# OpenSesame.net
KiCad netlist of a schematic drawn in EAGLE
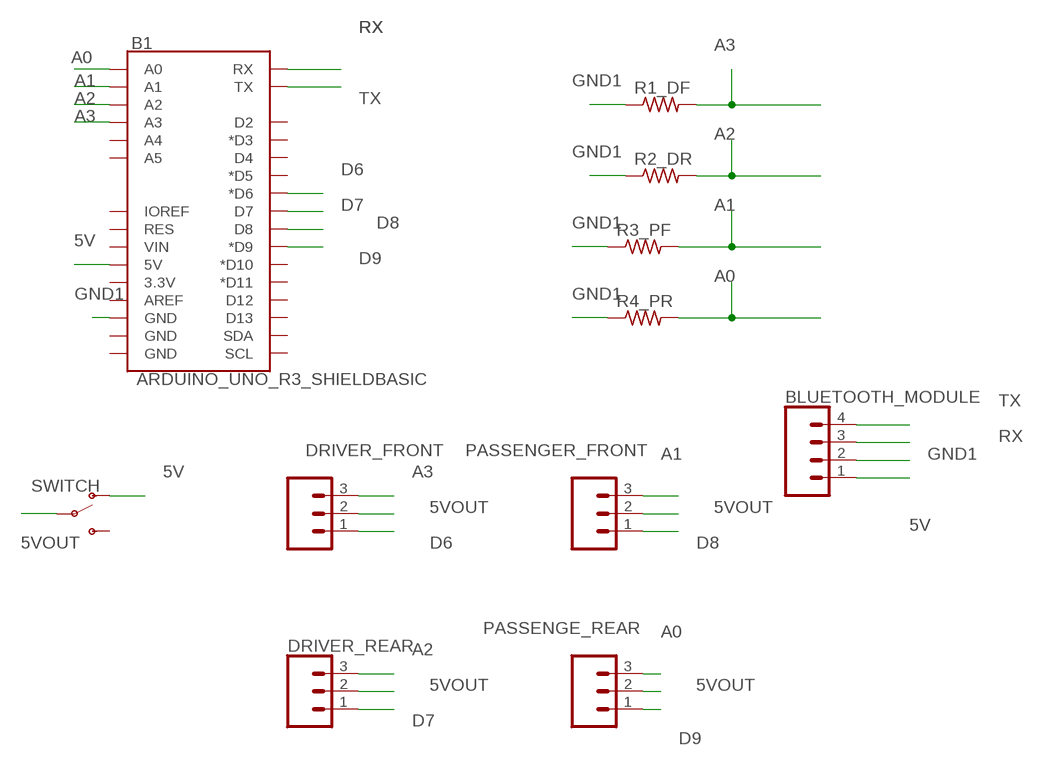
[diagram p0: schematic, sheet 1]

(export (version "E")
  (design (tool "Eeschema 10.0.6"))
  (components
    (comp (ref "B1")
      (value "ARDUINO_UNO_R3_SHIELDBASIC")
      (footprint "eagle-import:UNO_R3_SHIELD")
      (libsource (lib "eagle-import") (part "ARDUINO_UNO_R3_SHIELDBASIC"))
    )
    (comp (ref "BLUETOOTH_MODULE")
      (value "CONN_04")
      (footprint "eagle-import:1X04")
      (libsource (lib "eagle-import") (part "CONN_04"))
    )
    (comp (ref "DRIVER_FRONT")
      (value "CONN_03")
      (footprint "eagle-import:1X03")
      (libsource (lib "eagle-import") (part "CONN_03"))
    )
    (comp (ref "DRIVER_REAR")
      (value "CONN_03")
      (footprint "eagle-import:1X03")
      (libsource (lib "eagle-import") (part "CONN_03"))
    )
    (comp (ref "PASSENGER_FRONT")
      (value "CONN_03")
      (footprint "eagle-import:1X03")
      (libsource (lib "eagle-import") (part "CONN_03"))
    )
    (comp (ref "PASSENGE_REAR")
      (value "CONN_03")
      (footprint "eagle-import:1X03")
      (libsource (lib "eagle-import") (part "CONN_03"))
    )
    (comp (ref "R1_DF")
      (value "R-US_0204/7")
      (footprint "eagle-import:0204_7")
      (libsource (lib "eagle-import") (part "R-US_0204/7"))
    )
    (comp (ref "R2_DR")
      (value "R-US_0204/7")
      (footprint "eagle-import:0204_7")
      (libsource (lib "eagle-import") (part "R-US_0204/7"))
    )
    (comp (ref "R3_PF")
      (value "R-US_0204/7")
      (footprint "eagle-import:0204_7")
      (libsource (lib "eagle-import") (part "R-US_0204/7"))
    )
    (comp (ref "R4_PR")
      (value "R-US_0204/7")
      (footprint "eagle-import:0204_7")
      (libsource (lib "eagle-import") (part "R-US_0204/7"))
    )
    (comp (ref "SWITCH")
      (value "SWITCH-SPDT-PTH-11.6X4.0MM")
      (footprint "eagle-import:SWITCH_SPDT_PTH_11.6X4.0MM")
      (libsource (lib "eagle-import") (part "SWITCH-SPDT-PTH-11.6X4.0MM"))
    )
  )
  (nets
    (net (code "1") (name "/5V") (class "Default")
      (node (ref "B1") (pin "5V") (pinfunction "5V_5V") (pintype "bidirectional"))
      (node (ref "BLUETOOTH_MODULE") (pin "1") (pinfunction "1_1") (pintype "passive"))
      (node (ref "SWITCH") (pin "1") (pinfunction "O_1") (pintype "passive"))
    )
    (net (code "2") (name "/5VOUT") (class "Default")
      (node (ref "DRIVER_FRONT") (pin "2") (pinfunction "2_2") (pintype "passive"))
      (node (ref "DRIVER_REAR") (pin "2") (pinfunction "2_2") (pintype "passive"))
      (node (ref "PASSENGER_FRONT") (pin "2") (pinfunction "2_2") (pintype "passive"))
      (node (ref "PASSENGE_REAR") (pin "2") (pinfunction "2_2") (pintype "passive"))
      (node (ref "SWITCH") (pin "2") (pinfunction "P_2") (pintype "passive"))
    )
    (net (code "3") (name "/A0") (class "Default")
      (node (ref "B1") (pin "A0") (pinfunction "A0_A0") (pintype "bidirectional"))
      (node (ref "PASSENGE_REAR") (pin "3") (pinfunction "3_3") (pintype "passive"))
      (node (ref "R4_PR") (pin "2") (pinfunction "2_2") (pintype "passive"))
    )
    (net (code "4") (name "/A1") (class "Default")
      (node (ref "B1") (pin "A1") (pinfunction "A1_A1") (pintype "bidirectional"))
      (node (ref "PASSENGER_FRONT") (pin "3") (pinfunction "3_3") (pintype "passive"))
      (node (ref "R3_PF") (pin "2") (pinfunction "2_2") (pintype "passive"))
    )
    (net (code "5") (name "/A2") (class "Default")
      (node (ref "B1") (pin "A2") (pinfunction "A2_A2") (pintype "bidirectional"))
      (node (ref "DRIVER_REAR") (pin "3") (pinfunction "3_3") (pintype "passive"))
      (node (ref "R2_DR") (pin "2") (pinfunction "2_2") (pintype "passive"))
    )
    (net (code "6") (name "/A3") (class "Default")
      (node (ref "B1") (pin "A3") (pinfunction "A3_A3") (pintype "bidirectional"))
      (node (ref "DRIVER_FRONT") (pin "3") (pinfunction "3_3") (pintype "passive"))
      (node (ref "R1_DF") (pin "2") (pinfunction "2_2") (pintype "passive"))
    )
    (net (code "7") (name "/D6") (class "Default")
      (node (ref "B1") (pin "D6") (pinfunction "*D6_D6") (pintype "bidirectional"))
      (node (ref "DRIVER_FRONT") (pin "1") (pinfunction "1_1") (pintype "passive"))
    )
    (net (code "8") (name "/D7") (class "Default")
      (node (ref "B1") (pin "D7") (pinfunction "D7_D7") (pintype "bidirectional"))
      (node (ref "DRIVER_REAR") (pin "1") (pinfunction "1_1") (pintype "passive"))
    )
    (net (code "9") (name "/D8") (class "Default")
      (node (ref "B1") (pin "D8") (pinfunction "D8_D8") (pintype "bidirectional"))
      (node (ref "PASSENGER_FRONT") (pin "1") (pinfunction "1_1") (pintype "passive"))
    )
    (net (code "10") (name "/D9") (class "Default")
      (node (ref "B1") (pin "D9") (pinfunction "*D9_D9") (pintype "bidirectional"))
      (node (ref "PASSENGE_REAR") (pin "1") (pinfunction "1_1") (pintype "passive"))
    )
    (net (code "11") (name "/GND1") (class "Default")
      (node (ref "B1") (pin "GND@2") (pinfunction "GND_GND@2") (pintype "bidirectional"))
      (node (ref "BLUETOOTH_MODULE") (pin "2") (pinfunction "2_2") (pintype "passive"))
      (node (ref "R1_DF") (pin "1") (pinfunction "1_1") (pintype "passive"))
      (node (ref "R2_DR") (pin "1") (pinfunction "1_1") (pintype "passive"))
      (node (ref "R3_PF") (pin "1") (pinfunction "1_1") (pintype "passive"))
      (node (ref "R4_PR") (pin "1") (pinfunction "1_1") (pintype "passive"))
    )
    (net (code "12") (name "/RX") (class "Default")
      (node (ref "B1") (pin "RX") (pinfunction "RX_RX") (pintype "bidirectional"))
      (node (ref "BLUETOOTH_MODULE") (pin "3") (pinfunction "3_3") (pintype "passive"))
    )
    (net (code "13") (name "/TX") (class "Default")
      (node (ref "B1") (pin "TX") (pinfunction "TX_TX") (pintype "bidirectional"))
      (node (ref "BLUETOOTH_MODULE") (pin "4") (pinfunction "4_4") (pintype "passive"))
    )
    (net (code "14") (name "unconnected-(B1-*D3-PadD3)") (class "Default")
      (node (ref "B1") (pin "D3") (pinfunction "*D3_D3") (pintype "bidirectional"))
    )
    (net (code "15") (name "unconnected-(B1-*D5-PadD5)") (class "Default")
      (node (ref "B1") (pin "D5") (pinfunction "*D5_D5") (pintype "bidirectional"))
    )
    (net (code "16") (name "unconnected-(B1-*D10-PadD10)") (class "Default")
      (node (ref "B1") (pin "D10") (pinfunction "*D10_D10") (pintype "bidirectional"))
    )
    (net (code "17") (name "unconnected-(B1-*D11-PadD11)") (class "Default")
      (node (ref "B1") (pin "D11") (pinfunction "*D11_D11") (pintype "bidirectional"))
    )
    (net (code "18") (name "unconnected-(B1-GND-PadGND@0)") (class "Default")
      (node (ref "B1") (pin "GND@0") (pinfunction "GND_GND@0") (pintype "bidirectional"))
    )
    (net (code "19") (name "unconnected-(B1-GND-PadGND@1)") (class "Default")
      (node (ref "B1") (pin "GND@1") (pinfunction "GND_GND@1") (pintype "bidirectional"))
    )
    (net (code "20") (name "unconnected-(B1-Pad3.3V)") (class "Default")
      (node (ref "B1") (pin "3.3V") (pinfunction "3.3V_3.3V") (pintype "bidirectional"))
    )
    (net (code "21") (name "unconnected-(B1-PadA4)") (class "Default")
      (node (ref "B1") (pin "A4") (pinfunction "A4_A4") (pintype "bidirectional"))
    )
    (net (code "22") (name "unconnected-(B1-PadA5)") (class "Default")
      (node (ref "B1") (pin "A5") (pinfunction "A5_A5") (pintype "bidirectional"))
    )
    (net (code "23") (name "unconnected-(B1-PadAREF)") (class "Default")
      (node (ref "B1") (pin "AREF") (pinfunction "AREF_AREF") (pintype "bidirectional"))
    )
    (net (code "24") (name "unconnected-(B1-PadD2)") (class "Default")
      (node (ref "B1") (pin "D2") (pinfunction "D2_D2") (pintype "bidirectional"))
    )
    (net (code "25") (name "unconnected-(B1-PadD4)") (class "Default")
      (node (ref "B1") (pin "D4") (pinfunction "D4_D4") (pintype "bidirectional"))
    )
    (net (code "26") (name "unconnected-(B1-PadD12)") (class "Default")
      (node (ref "B1") (pin "D12") (pinfunction "D12_D12") (pintype "bidirectional"))
    )
    (net (code "27") (name "unconnected-(B1-PadD13)") (class "Default")
      (node (ref "B1") (pin "D13") (pinfunction "D13_D13") (pintype "bidirectional"))
    )
    (net (code "28") (name "unconnected-(B1-PadIOREF)") (class "Default")
      (node (ref "B1") (pin "IOREF") (pinfunction "IOREF_IOREF") (pintype "bidirectional"))
    )
    (net (code "29") (name "unconnected-(B1-PadRES)") (class "Default")
      (node (ref "B1") (pin "RES") (pinfunction "RES_RES") (pintype "bidirectional"))
    )
    (net (code "30") (name "unconnected-(B1-PadSCL)") (class "Default")
      (node (ref "B1") (pin "SCL") (pinfunction "SCL_SCL") (pintype "bidirectional"))
    )
    (net (code "31") (name "unconnected-(B1-PadSDA)") (class "Default")
      (node (ref "B1") (pin "SDA") (pinfunction "SDA_SDA") (pintype "bidirectional"))
    )
    (net (code "32") (name "unconnected-(B1-PadVIN)") (class "Default")
      (node (ref "B1") (pin "VIN") (pinfunction "VIN_VIN") (pintype "bidirectional"))
    )
    (net (code "33") (name "unconnected-(SWITCH-S-Pad3)") (class "Default")
      (node (ref "SWITCH") (pin "3") (pinfunction "S_3") (pintype "passive"))
    )
  )
)
